# pico_servo.net
KiCad netlist of a schematic drawn in EAGLE
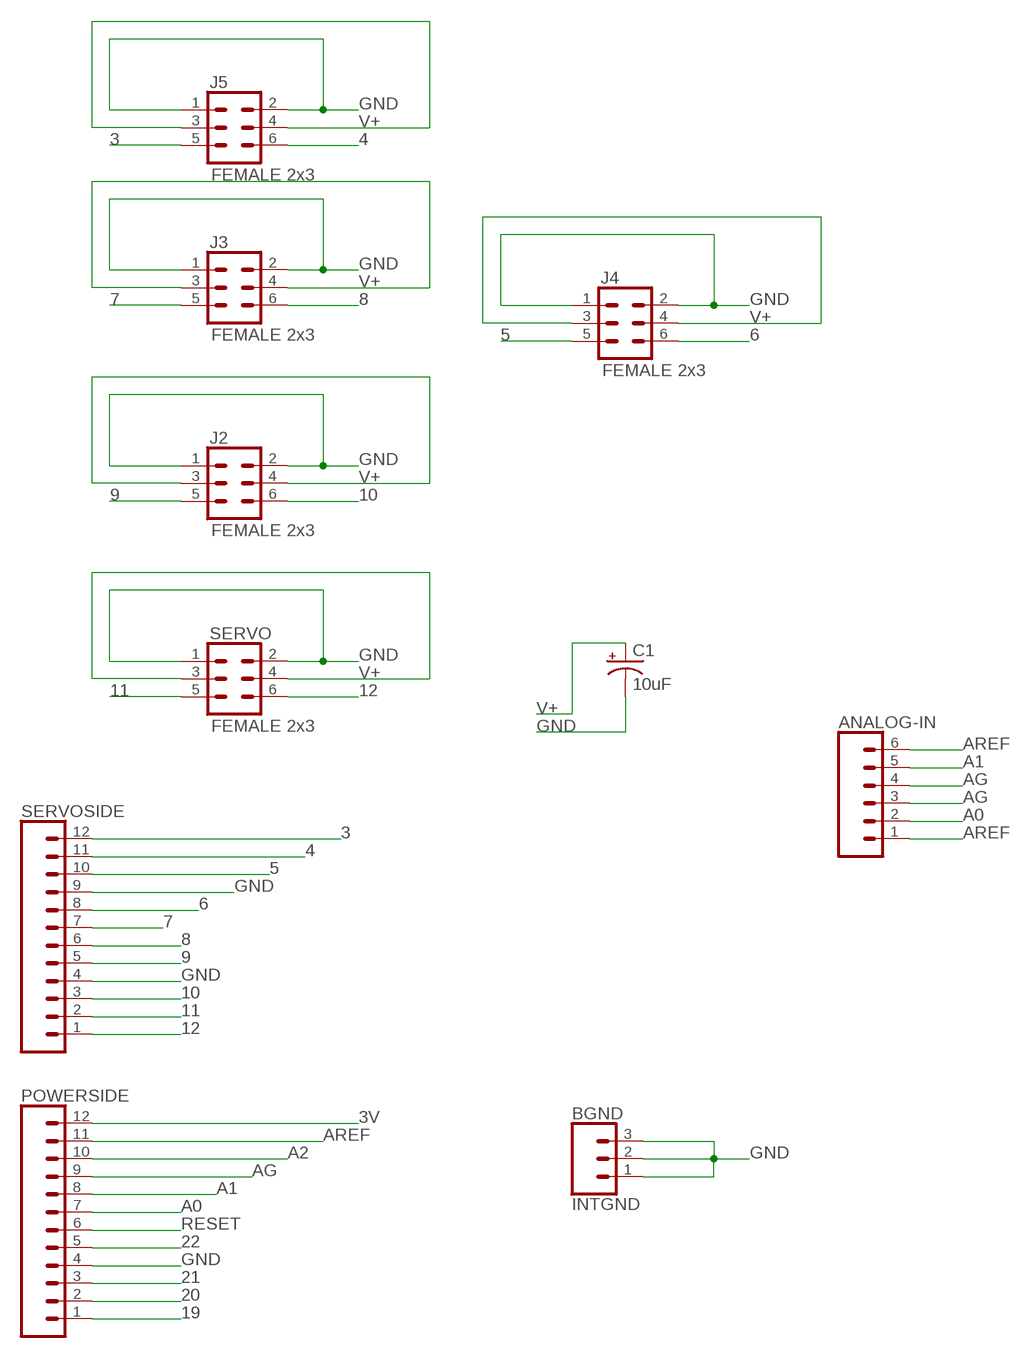
[diagram p0: schematic, sheet 1]

(export (version "E")
  (design (tool "Eeschema 10.0.6"))
  (components
    (comp (ref "ANALOG-IN")
      (value "CONN_06NO_SILK_FEMALE_PTH")
      (footprint "eagle-import:1X06_NO_SILK")
      (libsource (lib "eagle-import") (part "CONN_06NO_SILK_FEMALE_PTH"))
    )
    (comp (ref "BGND")
      (value "INTGND")
      (footprint "eagle-import:1X03")
      (libsource (lib "eagle-import") (part "CONN_03"))
    )
    (comp (ref "C1")
      (value "10uF")
      (footprint "eagle-import:CPOL-RADIAL-2.5MM-5MM")
      (libsource (lib "eagle-import") (part "10UF-POLAR-RADIAL-2.5MM-25V-20%"))
    )
    (comp (ref "J2")
      (value "FEMALE 2x3")
      (footprint "eagle-import:2X3")
      (libsource (lib "eagle-import") (part "CONN_03X2FEMALE"))
    )
    (comp (ref "J3")
      (value "FEMALE 2x3")
      (footprint "eagle-import:2X3")
      (libsource (lib "eagle-import") (part "CONN_03X2FEMALE"))
    )
    (comp (ref "J4")
      (value "FEMALE 2x3")
      (footprint "eagle-import:2X3")
      (libsource (lib "eagle-import") (part "CONN_03X2FEMALE"))
    )
    (comp (ref "J5")
      (value "FEMALE 2x3")
      (footprint "eagle-import:2X3")
      (libsource (lib "eagle-import") (part "CONN_03X2FEMALE"))
    )
    (comp (ref "POWERSIDE")
      (value "CONN_12LONGPADS")
      (footprint "eagle-import:1X12_LONGPADS")
      (libsource (lib "eagle-import") (part "CONN_12LONGPADS"))
    )
    (comp (ref "SERVO")
      (value "FEMALE 2x3")
      (footprint "eagle-import:2X3")
      (libsource (lib "eagle-import") (part "CONN_03X2FEMALE"))
    )
    (comp (ref "SERVOSIDE")
      (value "CONN_12LONGPADS")
      (footprint "eagle-import:1X12_LONGPADS")
      (libsource (lib "eagle-import") (part "CONN_12LONGPADS"))
    )
  )
  (nets
    (net (code "1") (name "/3") (class "Default")
      (node (ref "J5") (pin "5") (pinfunction "5_5") (pintype "bidirectional"))
      (node (ref "SERVOSIDE") (pin "12") (pinfunction "12_12") (pintype "passive"))
    )
    (net (code "2") (name "/3V") (class "Default")
      (node (ref "POWERSIDE") (pin "12") (pinfunction "12_12") (pintype "passive"))
    )
    (net (code "3") (name "/4") (class "Default")
      (node (ref "J5") (pin "6") (pinfunction "6_6") (pintype "bidirectional"))
      (node (ref "SERVOSIDE") (pin "11") (pinfunction "11_11") (pintype "passive"))
    )
    (net (code "4") (name "/5") (class "Default")
      (node (ref "J4") (pin "5") (pinfunction "5_5") (pintype "bidirectional"))
      (node (ref "SERVOSIDE") (pin "10") (pinfunction "10_10") (pintype "passive"))
    )
    (net (code "5") (name "/6") (class "Default")
      (node (ref "J4") (pin "6") (pinfunction "6_6") (pintype "bidirectional"))
      (node (ref "SERVOSIDE") (pin "8") (pinfunction "8_8") (pintype "passive"))
    )
    (net (code "6") (name "/7") (class "Default")
      (node (ref "J3") (pin "5") (pinfunction "5_5") (pintype "bidirectional"))
      (node (ref "SERVOSIDE") (pin "7") (pinfunction "7_7") (pintype "passive"))
    )
    (net (code "7") (name "/8") (class "Default")
      (node (ref "J3") (pin "6") (pinfunction "6_6") (pintype "bidirectional"))
      (node (ref "SERVOSIDE") (pin "6") (pinfunction "6_6") (pintype "passive"))
    )
    (net (code "8") (name "/9") (class "Default")
      (node (ref "J2") (pin "5") (pinfunction "5_5") (pintype "bidirectional"))
      (node (ref "SERVOSIDE") (pin "5") (pinfunction "5_5") (pintype "passive"))
    )
    (net (code "9") (name "/10") (class "Default")
      (node (ref "J2") (pin "6") (pinfunction "6_6") (pintype "bidirectional"))
      (node (ref "SERVOSIDE") (pin "3") (pinfunction "3_3") (pintype "passive"))
    )
    (net (code "10") (name "/11") (class "Default")
      (node (ref "SERVO") (pin "5") (pinfunction "5_5") (pintype "bidirectional"))
      (node (ref "SERVOSIDE") (pin "2") (pinfunction "2_2") (pintype "passive"))
    )
    (net (code "11") (name "/12") (class "Default")
      (node (ref "SERVO") (pin "6") (pinfunction "6_6") (pintype "bidirectional"))
      (node (ref "SERVOSIDE") (pin "1") (pinfunction "1_1") (pintype "passive"))
    )
    (net (code "12") (name "/19") (class "Default")
      (node (ref "POWERSIDE") (pin "1") (pinfunction "1_1") (pintype "passive"))
    )
    (net (code "13") (name "/20") (class "Default")
      (node (ref "POWERSIDE") (pin "2") (pinfunction "2_2") (pintype "passive"))
    )
    (net (code "14") (name "/21") (class "Default")
      (node (ref "POWERSIDE") (pin "3") (pinfunction "3_3") (pintype "passive"))
    )
    (net (code "15") (name "/22") (class "Default")
      (node (ref "POWERSIDE") (pin "5") (pinfunction "5_5") (pintype "passive"))
    )
    (net (code "16") (name "/A0") (class "Default")
      (node (ref "ANALOG-IN") (pin "2") (pinfunction "2_2") (pintype "passive"))
      (node (ref "POWERSIDE") (pin "7") (pinfunction "7_7") (pintype "passive"))
    )
    (net (code "17") (name "/A1") (class "Default")
      (node (ref "ANALOG-IN") (pin "5") (pinfunction "5_5") (pintype "passive"))
      (node (ref "POWERSIDE") (pin "8") (pinfunction "8_8") (pintype "passive"))
    )
    (net (code "18") (name "/A2") (class "Default")
      (node (ref "POWERSIDE") (pin "10") (pinfunction "10_10") (pintype "passive"))
    )
    (net (code "19") (name "/AG") (class "Default")
      (node (ref "ANALOG-IN") (pin "3") (pinfunction "3_3") (pintype "passive"))
      (node (ref "ANALOG-IN") (pin "4") (pinfunction "4_4") (pintype "passive"))
      (node (ref "POWERSIDE") (pin "9") (pinfunction "9_9") (pintype "passive"))
    )
    (net (code "20") (name "/AREF") (class "Default")
      (node (ref "ANALOG-IN") (pin "1") (pinfunction "1_1") (pintype "passive"))
      (node (ref "ANALOG-IN") (pin "6") (pinfunction "6_6") (pintype "passive"))
      (node (ref "POWERSIDE") (pin "11") (pinfunction "11_11") (pintype "passive"))
    )
    (net (code "21") (name "/GND") (class "Default")
      (node (ref "BGND") (pin "1") (pinfunction "1_1") (pintype "passive"))
      (node (ref "BGND") (pin "2") (pinfunction "2_2") (pintype "passive"))
      (node (ref "BGND") (pin "3") (pinfunction "3_3") (pintype "passive"))
      (node (ref "C1") (pin "2") (pinfunction "-_2") (pintype "passive"))
      (node (ref "J2") (pin "1") (pinfunction "1_1") (pintype "bidirectional"))
      (node (ref "J2") (pin "2") (pinfunction "2_2") (pintype "bidirectional"))
      (node (ref "J3") (pin "1") (pinfunction "1_1") (pintype "bidirectional"))
      (node (ref "J3") (pin "2") (pinfunction "2_2") (pintype "bidirectional"))
      (node (ref "J4") (pin "1") (pinfunction "1_1") (pintype "bidirectional"))
      (node (ref "J4") (pin "2") (pinfunction "2_2") (pintype "bidirectional"))
      (node (ref "J5") (pin "1") (pinfunction "1_1") (pintype "bidirectional"))
      (node (ref "J5") (pin "2") (pinfunction "2_2") (pintype "bidirectional"))
      (node (ref "POWERSIDE") (pin "4") (pinfunction "4_4") (pintype "passive"))
      (node (ref "SERVO") (pin "1") (pinfunction "1_1") (pintype "bidirectional"))
      (node (ref "SERVO") (pin "2") (pinfunction "2_2") (pintype "bidirectional"))
      (node (ref "SERVOSIDE") (pin "4") (pinfunction "4_4") (pintype "passive"))
      (node (ref "SERVOSIDE") (pin "9") (pinfunction "9_9") (pintype "passive"))
    )
    (net (code "22") (name "/RESET") (class "Default")
      (node (ref "POWERSIDE") (pin "6") (pinfunction "6_6") (pintype "passive"))
    )
    (net (code "23") (name "/V+") (class "Default")
      (node (ref "C1") (pin "1") (pinfunction "+_1") (pintype "passive"))
      (node (ref "J2") (pin "3") (pinfunction "3_3") (pintype "bidirectional"))
      (node (ref "J2") (pin "4") (pinfunction "4_4") (pintype "bidirectional"))
      (node (ref "J3") (pin "3") (pinfunction "3_3") (pintype "bidirectional"))
      (node (ref "J3") (pin "4") (pinfunction "4_4") (pintype "bidirectional"))
      (node (ref "J4") (pin "3") (pinfunction "3_3") (pintype "bidirectional"))
      (node (ref "J4") (pin "4") (pinfunction "4_4") (pintype "bidirectional"))
      (node (ref "J5") (pin "3") (pinfunction "3_3") (pintype "bidirectional"))
      (node (ref "J5") (pin "4") (pinfunction "4_4") (pintype "bidirectional"))
      (node (ref "SERVO") (pin "3") (pinfunction "3_3") (pintype "bidirectional"))
      (node (ref "SERVO") (pin "4") (pinfunction "4_4") (pintype "bidirectional"))
    )
  )
)
